# -12V_PSU.net
KiCad netlist of a schematic drawn in EAGLE
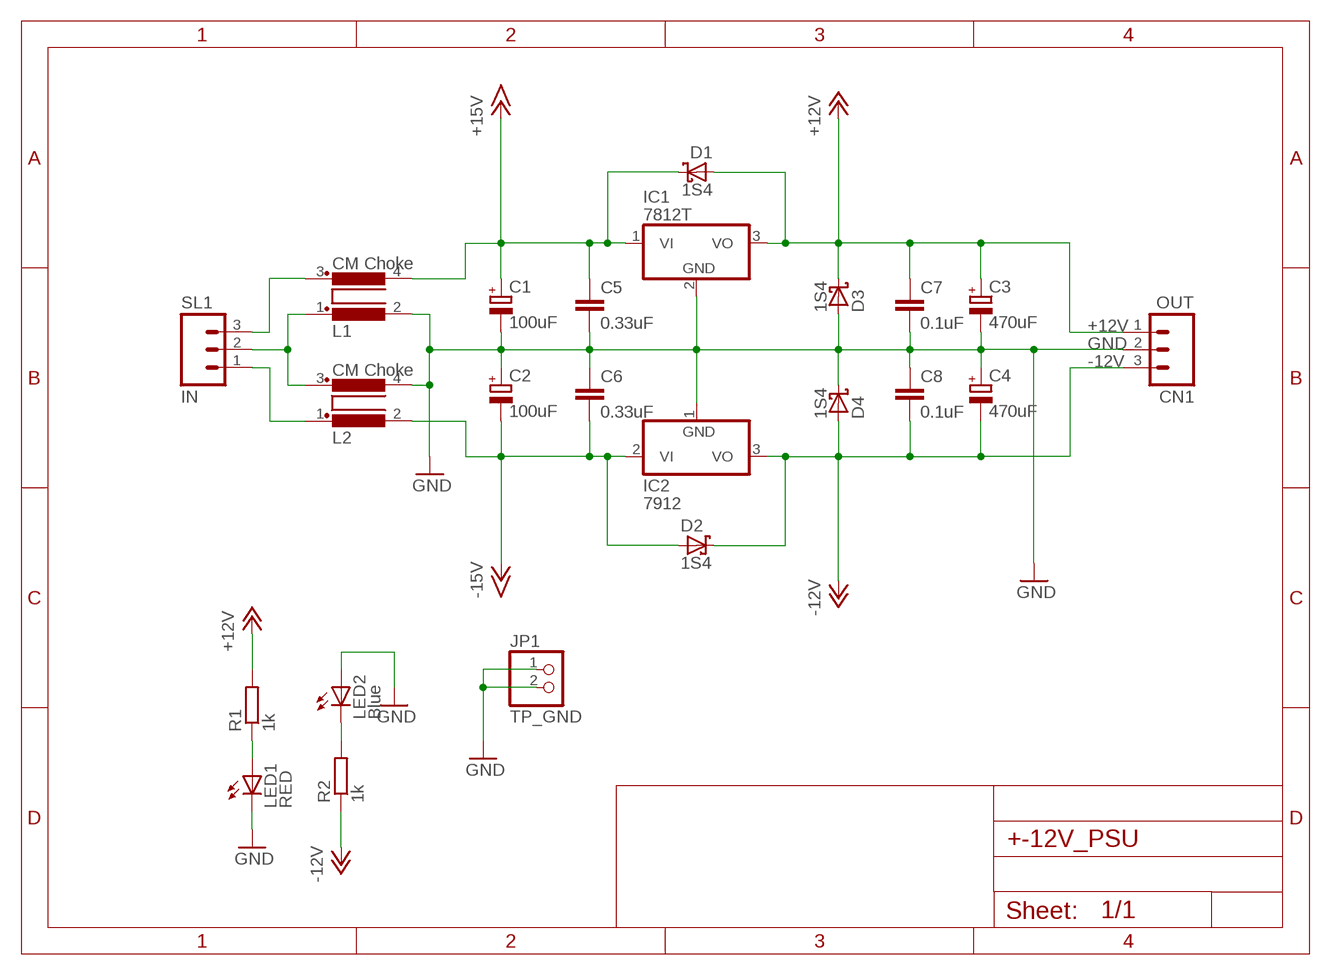
[diagram p0: schematic, sheet 1]

(export (version "E")
  (design (tool "Eeschema 10.0.6"))
  (components
    (comp (ref "C1")
      (value "100uF")
      (footprint "eagle-import:E2,5-7")
      (libsource (lib "eagle-import") (part "CPOL-EUE2.5-7"))
    )
    (comp (ref "C2")
      (value "100uF")
      (footprint "eagle-import:E2,5-7")
      (libsource (lib "eagle-import") (part "CPOL-EUE2.5-7"))
    )
    (comp (ref "C3")
      (value "470uF")
      (footprint "eagle-import:E7,5-16")
      (libsource (lib "eagle-import") (part "CPOL-EUE7.5-16"))
    )
    (comp (ref "C4")
      (value "470uF")
      (footprint "eagle-import:E7,5-16")
      (libsource (lib "eagle-import") (part "CPOL-EUE7.5-16"))
    )
    (comp (ref "C5")
      (value "0.33uF")
      (footprint "eagle-import:C025-024X044")
      (libsource (lib "eagle-import") (part "C-EU025-024X044"))
    )
    (comp (ref "C6")
      (value "0.33uF")
      (footprint "eagle-import:C025-024X044")
      (libsource (lib "eagle-import") (part "C-EU025-024X044"))
    )
    (comp (ref "C7")
      (value "0.1uF")
      (footprint "eagle-import:C025-024X044")
      (libsource (lib "eagle-import") (part "C-EU025-024X044"))
    )
    (comp (ref "C8")
      (value "0.1uF")
      (footprint "eagle-import:C025-024X044")
      (libsource (lib "eagle-import") (part "C-EU025-024X044"))
    )
    (comp (ref "CN1")
      (value "OUT")
      (footprint "eagle-import:03PA")
      (libsource (lib "eagle-import") (part "AMP-EI-M3"))
    )
    (comp (ref "D1")
      (value "1S4")
      (footprint "eagle-import:DO35-7")
      (libsource (lib "eagle-import") (part "SCHOTTKY-DIODEDO35-7"))
    )
    (comp (ref "D2")
      (value "1S4")
      (footprint "eagle-import:DO35-7")
      (libsource (lib "eagle-import") (part "SCHOTTKY-DIODEDO35-7"))
    )
    (comp (ref "D3")
      (value "1S4")
      (footprint "eagle-import:DO35-7")
      (libsource (lib "eagle-import") (part "SCHOTTKY-DIODEDO35-7"))
    )
    (comp (ref "D4")
      (value "1S4")
      (footprint "eagle-import:DO35-7")
      (libsource (lib "eagle-import") (part "SCHOTTKY-DIODEDO35-7"))
    )
    (comp (ref "IC1")
      (value "7812T")
      (footprint "eagle-import:TO220H")
      (libsource (lib "eagle-import") (part "78T12"))
    )
    (comp (ref "IC2")
      (value "7912")
      (footprint "eagle-import:TO220H")
      (libsource (lib "eagle-import") (part "79T12"))
    )
    (comp (ref "JP1")
      (value "TP_GND")
      (footprint "eagle-import:1X02")
      (libsource (lib "eagle-import") (part "PINHD-1X2"))
    )
    (comp (ref "L1")
      (value "CM Choke")
      (footprint "eagle-import:EV20")
      (libsource (lib "eagle-import") (part "EV20"))
    )
    (comp (ref "L2")
      (value "CM Choke")
      (footprint "eagle-import:EV20")
      (libsource (lib "eagle-import") (part "EV20"))
    )
    (comp (ref "LED1")
      (value "RED")
      (footprint "eagle-import:LED3MM")
      (libsource (lib "eagle-import") (part "LED3MM"))
    )
    (comp (ref "LED2")
      (value "Blue")
      (footprint "eagle-import:LED3MM")
      (libsource (lib "eagle-import") (part "LED3MM"))
    )
    (comp (ref "R1")
      (value "1k")
      (footprint "eagle-import:0207_7")
      (libsource (lib "eagle-import") (part "R-EU_0207/7"))
    )
    (comp (ref "R2")
      (value "1k")
      (footprint "eagle-import:0207_7")
      (libsource (lib "eagle-import") (part "R-EU_0207/7"))
    )
    (comp (ref "SL1")
      (value "IN")
      (footprint "eagle-import:03PA")
      (libsource (lib "eagle-import") (part "AMP-EI-M3"))
    )
  )
  (nets
    (net (code "1") (name "+12V") (class "Default")
      (node (ref "C3") (pin "+") (pinfunction "+_+") (pintype "passive"))
      (node (ref "C7") (pin "1") (pinfunction "1_1") (pintype "passive"))
      (node (ref "CN1") (pin "1") (pinfunction "1_1") (pintype "passive"))
      (node (ref "D1") (pin "A") (pinfunction "A_A") (pintype "passive"))
      (node (ref "D3") (pin "C") (pinfunction "C_C") (pintype "passive"))
      (node (ref "IC1") (pin "3") (pinfunction "VO_3") (pintype "passive"))
      (node (ref "R1") (pin "2") (pinfunction "2_2") (pintype "passive"))
    )
    (net (code "2") (name "+15V") (class "Default")
      (node (ref "C1") (pin "+") (pinfunction "+_+") (pintype "passive"))
      (node (ref "C5") (pin "1") (pinfunction "1_1") (pintype "passive"))
      (node (ref "D1") (pin "C") (pinfunction "C_C") (pintype "passive"))
      (node (ref "IC1") (pin "1") (pinfunction "VI_1") (pintype "input"))
      (node (ref "L1") (pin "4") (pinfunction "4_4") (pintype "passive"))
    )
    (net (code "3") (name "-12V") (class "Default")
      (node (ref "C4") (pin "-") (pinfunction "-_-") (pintype "passive"))
      (node (ref "C8") (pin "2") (pinfunction "2_2") (pintype "passive"))
      (node (ref "CN1") (pin "3") (pinfunction "3_3") (pintype "passive"))
      (node (ref "D2") (pin "C") (pinfunction "C_C") (pintype "passive"))
      (node (ref "D4") (pin "A") (pinfunction "A_A") (pintype "passive"))
      (node (ref "IC2") (pin "3") (pinfunction "VO_3") (pintype "passive"))
      (node (ref "R2") (pin "1") (pinfunction "1_1") (pintype "passive"))
    )
    (net (code "4") (name "-15V") (class "Default")
      (node (ref "C2") (pin "-") (pinfunction "-_-") (pintype "passive"))
      (node (ref "C6") (pin "2") (pinfunction "2_2") (pintype "passive"))
      (node (ref "D2") (pin "A") (pinfunction "A_A") (pintype "passive"))
      (node (ref "IC2") (pin "2") (pinfunction "VI_2") (pintype "input"))
      (node (ref "L2") (pin "2") (pinfunction "2_2") (pintype "passive"))
    )
    (net (code "5") (name "GND") (class "Default")
      (node (ref "C1") (pin "-") (pinfunction "-_-") (pintype "passive"))
      (node (ref "C2") (pin "+") (pinfunction "+_+") (pintype "passive"))
      (node (ref "C3") (pin "-") (pinfunction "-_-") (pintype "passive"))
      (node (ref "C4") (pin "+") (pinfunction "+_+") (pintype "passive"))
      (node (ref "C5") (pin "2") (pinfunction "2_2") (pintype "passive"))
      (node (ref "C6") (pin "1") (pinfunction "1_1") (pintype "passive"))
      (node (ref "C7") (pin "2") (pinfunction "2_2") (pintype "passive"))
      (node (ref "C8") (pin "1") (pinfunction "1_1") (pintype "passive"))
      (node (ref "CN1") (pin "2") (pinfunction "2_2") (pintype "passive"))
      (node (ref "D3") (pin "A") (pinfunction "A_A") (pintype "passive"))
      (node (ref "D4") (pin "C") (pinfunction "C_C") (pintype "passive"))
      (node (ref "IC1") (pin "2") (pinfunction "GND_2") (pintype "passive"))
      (node (ref "IC2") (pin "1") (pinfunction "GND_1") (pintype "passive"))
      (node (ref "JP1") (pin "1") (pinfunction "1_1") (pintype "passive"))
      (node (ref "JP1") (pin "2") (pinfunction "2_2") (pintype "passive"))
      (node (ref "L1") (pin "2") (pinfunction "2_2") (pintype "passive"))
      (node (ref "L2") (pin "4") (pinfunction "4_4") (pintype "passive"))
      (node (ref "LED1") (pin "K") (pinfunction "C_K") (pintype "passive"))
      (node (ref "LED2") (pin "A") (pinfunction "A_A") (pintype "passive"))
    )
    (net (code "6") (name "Net-(L1-Pad1)") (class "Default")
      (node (ref "L1") (pin "1") (pinfunction "1_1") (pintype "passive"))
      (node (ref "L2") (pin "3") (pinfunction "3_3") (pintype "passive"))
      (node (ref "SL1") (pin "2") (pinfunction "2_2") (pintype "passive"))
    )
    (net (code "7") (name "Net-(L1-Pad3)") (class "Default")
      (node (ref "L1") (pin "3") (pinfunction "3_3") (pintype "passive"))
      (node (ref "SL1") (pin "3") (pinfunction "3_3") (pintype "passive"))
    )
    (net (code "8") (name "Net-(L2-Pad1)") (class "Default")
      (node (ref "L2") (pin "1") (pinfunction "1_1") (pintype "passive"))
      (node (ref "SL1") (pin "1") (pinfunction "1_1") (pintype "passive"))
    )
    (net (code "9") (name "Net-(LED1-PadA)") (class "Default")
      (node (ref "LED1") (pin "A") (pinfunction "A_A") (pintype "passive"))
      (node (ref "R1") (pin "1") (pinfunction "1_1") (pintype "passive"))
    )
    (net (code "10") (name "Net-(LED2-C)") (class "Default")
      (node (ref "LED2") (pin "K") (pinfunction "C_K") (pintype "passive"))
      (node (ref "R2") (pin "2") (pinfunction "2_2") (pintype "passive"))
    )
  )
)
